# Sheet2.net
KiCad netlist of a schematic drawn in Altium Designer
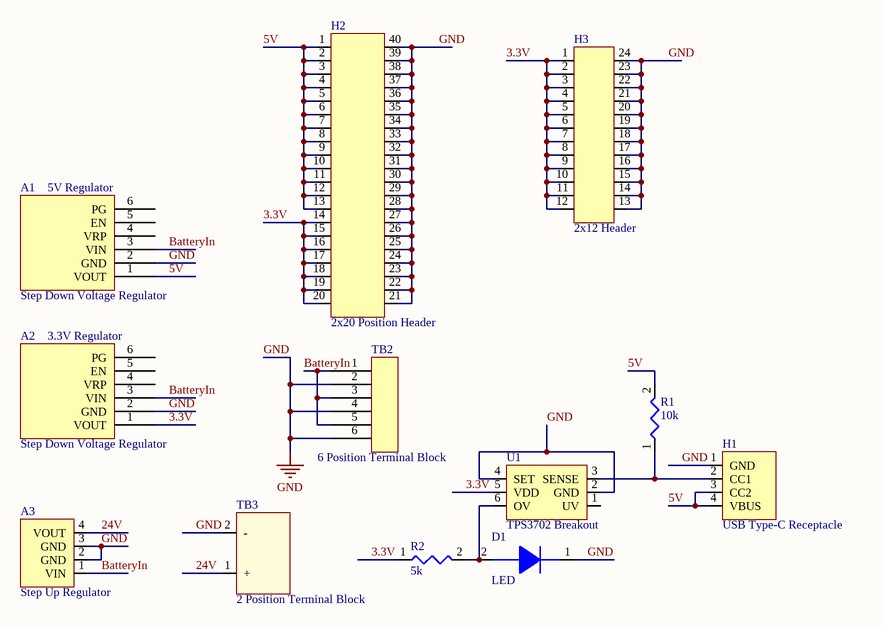
[diagram p0: Sheet2.SchDoc]

(export (version "E")
  (design (tool "Eeschema 10.0.6"))
  (components
    (comp (ref "A1")
      (value "Step Down Voltage Regulator")
      (footprint "New Volt Reg TEMPLATE")
      (libsource (lib "Schlib2") (part "Step Down Voltage Regulator"))
    )
    (comp (ref "A2")
      (value "Step Down Voltage Regulator")
      (footprint "New Volt Reg TEMPLATE")
      (libsource (lib "Schlib2") (part "Step Down Voltage Regulator"))
    )
    (comp (ref "A3")
      (value "Step Up Regulator")
      (footprint "24V STEP UP REGULATOR")
      (libsource (lib "Schlib2") (part "Step Up Regulator"))
    )
    (comp (ref "D1") (value "LED") (footprint "LED") (libsource (lib "Schlib2") (part "LED")))
    (comp (ref "H1")
      (value "USB Type-C Receptacle")
      (footprint "USB Type-C Receptacle")
      (libsource (lib "Schlib2") (part "USB Type-C Receptacle"))
    )
    (comp (ref "H2")
      (value "2x20 Position Header")
      (footprint "2x20 Header")
      (libsource (lib "Schlib2") (part "2x20 Position Header"))
    )
    (comp (ref "H3")
      (value "2x12 Header")
      (footprint "2x12 HEADER")
      (libsource (lib "Schlib2") (part "2x12 Header"))
    )
    (comp (ref "R1") (value "10k") (footprint "Resistor") (libsource (lib "Schlib2") (part "Resistor")))
    (comp (ref "R2") (value "5k") (footprint "Resistor") (libsource (lib "Schlib2") (part "Resistor")))
    (comp (ref "TB2")
      (value "6 Position Terminal Block")
      (footprint "NEW 6 Terminal")
      (libsource (lib "Schlib2") (part "6 Position Terminal Block"))
    )
    (comp (ref "TB3")
      (value "2 Position Terminal Block")
      (footprint "Terminal Block")
      (libsource (lib "Schlib2") (part "2 Position Terminal Block"))
    )
    (comp (ref "U1")
      (value "TPS3702 Breakout")
      (footprint "TPS3702 Breakout")
      (libsource (lib "Schlib2") (part "TPS3702 Breakout"))
    )
  )
  (nets
    (net (code "1") (name "/3.3V") (class "Default")
      (node (ref "A2") (pin "1") (pinfunction "VOUT_1") (pintype "passive"))
      (node (ref "H2") (pin "14") (pinfunction "14_14") (pintype "passive"))
      (node (ref "H2") (pin "15") (pinfunction "15_15") (pintype "passive"))
      (node (ref "H2") (pin "16") (pinfunction "16_16") (pintype "passive"))
      (node (ref "H2") (pin "17") (pinfunction "17_17") (pintype "passive"))
      (node (ref "H2") (pin "18") (pinfunction "18_18") (pintype "passive"))
      (node (ref "H2") (pin "19") (pinfunction "19_19") (pintype "passive"))
      (node (ref "H2") (pin "20") (pinfunction "20_20") (pintype "passive"))
      (node (ref "H3") (pin "1") (pinfunction "1_1") (pintype "passive"))
      (node (ref "H3") (pin "10") (pinfunction "10_10") (pintype "passive"))
      (node (ref "H3") (pin "11") (pinfunction "11_11") (pintype "passive"))
      (node (ref "H3") (pin "12") (pinfunction "12_12") (pintype "passive"))
      (node (ref "H3") (pin "2") (pinfunction "2_2") (pintype "passive"))
      (node (ref "H3") (pin "3") (pinfunction "3_3") (pintype "passive"))
      (node (ref "H3") (pin "4") (pinfunction "4_4") (pintype "passive"))
      (node (ref "H3") (pin "5") (pinfunction "5_5") (pintype "passive"))
      (node (ref "H3") (pin "6") (pinfunction "6_6") (pintype "passive"))
      (node (ref "H3") (pin "7") (pinfunction "7_7") (pintype "passive"))
      (node (ref "H3") (pin "8") (pinfunction "8_8") (pintype "passive"))
      (node (ref "H3") (pin "9") (pinfunction "9_9") (pintype "passive"))
      (node (ref "R2") (pin "1") (pinfunction "1_1") (pintype "passive"))
      (node (ref "U1") (pin "5") (pinfunction "VDD_5") (pintype "passive"))
    )
    (net (code "2") (name "/5V") (class "Default")
      (node (ref "A1") (pin "1") (pinfunction "VOUT_1") (pintype "passive"))
      (node (ref "H1") (pin "3") (pinfunction "CC2_3") (pintype "passive"))
      (node (ref "H1") (pin "4") (pinfunction "VBUS_4") (pintype "passive"))
      (node (ref "H2") (pin "1") (pinfunction "1_1") (pintype "passive"))
      (node (ref "H2") (pin "10") (pinfunction "10_10") (pintype "passive"))
      (node (ref "H2") (pin "11") (pinfunction "11_11") (pintype "passive"))
      (node (ref "H2") (pin "12") (pinfunction "12_12") (pintype "passive"))
      (node (ref "H2") (pin "13") (pinfunction "13_13") (pintype "passive"))
      (node (ref "H2") (pin "2") (pinfunction "2_2") (pintype "passive"))
      (node (ref "H2") (pin "3") (pinfunction "3_3") (pintype "passive"))
      (node (ref "H2") (pin "4") (pinfunction "4_4") (pintype "passive"))
      (node (ref "H2") (pin "5") (pinfunction "5_5") (pintype "passive"))
      (node (ref "H2") (pin "6") (pinfunction "6_6") (pintype "passive"))
      (node (ref "H2") (pin "7") (pinfunction "7_7") (pintype "passive"))
      (node (ref "H2") (pin "8") (pinfunction "8_8") (pintype "passive"))
      (node (ref "H2") (pin "9") (pinfunction "9_9") (pintype "passive"))
      (node (ref "R1") (pin "2") (pinfunction "2_2") (pintype "passive"))
    )
    (net (code "3") (name "/24V") (class "Default")
      (node (ref "A3") (pin "4") (pinfunction "VOUT_4") (pintype "passive"))
      (node (ref "TB3") (pin "1") (pinfunction "+_1") (pintype "passive"))
    )
    (net (code "4") (name "/BatteryIn") (class "Default")
      (node (ref "A1") (pin "3") (pinfunction "VIN_3") (pintype "passive"))
      (node (ref "A2") (pin "3") (pinfunction "VIN_3") (pintype "passive"))
      (node (ref "A3") (pin "1") (pinfunction "VIN_1") (pintype "passive"))
      (node (ref "TB2") (pin "1") (pintype "passive"))
      (node (ref "TB2") (pin "3") (pintype "passive"))
      (node (ref "TB2") (pin "5") (pintype "passive"))
    )
    (net (code "5") (name "GND") (class "Default")
      (node (ref "A1") (pin "2") (pinfunction "GND_2") (pintype "passive"))
      (node (ref "A2") (pin "2") (pinfunction "GND_2") (pintype "passive"))
      (node (ref "A3") (pin "2") (pinfunction "GND_2") (pintype "passive"))
      (node (ref "A3") (pin "3") (pinfunction "GND_3") (pintype "passive"))
      (node (ref "D1") (pin "1") (pinfunction "Anode_1") (pintype "passive"))
      (node (ref "H1") (pin "1") (pinfunction "GND_1") (pintype "passive"))
      (node (ref "H2") (pin "21") (pinfunction "21_21") (pintype "passive"))
      (node (ref "H2") (pin "22") (pinfunction "22_22") (pintype "passive"))
      (node (ref "H2") (pin "23") (pinfunction "23_23") (pintype "passive"))
      (node (ref "H2") (pin "24") (pinfunction "24_24") (pintype "passive"))
      (node (ref "H2") (pin "25") (pinfunction "25_25") (pintype "passive"))
      (node (ref "H2") (pin "26") (pinfunction "26_26") (pintype "passive"))
      (node (ref "H2") (pin "27") (pinfunction "27_27") (pintype "passive"))
      (node (ref "H2") (pin "28") (pinfunction "28_28") (pintype "passive"))
      (node (ref "H2") (pin "29") (pinfunction "29_29") (pintype "passive"))
      (node (ref "H2") (pin "30") (pinfunction "30_30") (pintype "passive"))
      (node (ref "H2") (pin "31") (pinfunction "31_31") (pintype "passive"))
      (node (ref "H2") (pin "32") (pinfunction "32_32") (pintype "passive"))
      (node (ref "H2") (pin "33") (pinfunction "33_33") (pintype "passive"))
      (node (ref "H2") (pin "34") (pinfunction "34_34") (pintype "passive"))
      (node (ref "H2") (pin "35") (pinfunction "35_35") (pintype "passive"))
      (node (ref "H2") (pin "36") (pinfunction "36_36") (pintype "passive"))
      (node (ref "H2") (pin "37") (pinfunction "37_37") (pintype "passive"))
      (node (ref "H2") (pin "38") (pinfunction "38_38") (pintype "passive"))
      (node (ref "H2") (pin "39") (pinfunction "39_39") (pintype "passive"))
      (node (ref "H2") (pin "40") (pinfunction "40_40") (pintype "passive"))
      (node (ref "H3") (pin "13") (pinfunction "13_13") (pintype "passive"))
      (node (ref "H3") (pin "14") (pinfunction "14_14") (pintype "passive"))
      (node (ref "H3") (pin "15") (pinfunction "15_15") (pintype "passive"))
      (node (ref "H3") (pin "16") (pinfunction "16_16") (pintype "passive"))
      (node (ref "H3") (pin "17") (pinfunction "17_17") (pintype "passive"))
      (node (ref "H3") (pin "18") (pinfunction "18_18") (pintype "passive"))
      (node (ref "H3") (pin "19") (pinfunction "19_19") (pintype "passive"))
      (node (ref "H3") (pin "20") (pinfunction "20_20") (pintype "passive"))
      (node (ref "H3") (pin "21") (pinfunction "21_21") (pintype "passive"))
      (node (ref "H3") (pin "22") (pinfunction "22_22") (pintype "passive"))
      (node (ref "H3") (pin "23") (pinfunction "23_23") (pintype "passive"))
      (node (ref "H3") (pin "24") (pinfunction "24_24") (pintype "passive"))
      (node (ref "TB2") (pin "2") (pintype "passive"))
      (node (ref "TB2") (pin "4") (pintype "passive"))
      (node (ref "TB2") (pin "6") (pintype "passive"))
      (node (ref "TB3") (pin "2") (pinfunction "-_2") (pintype "passive"))
      (node (ref "U1") (pin "2") (pinfunction "GND_2") (pintype "passive"))
      (node (ref "U1") (pin "4") (pinfunction "SET_4") (pintype "passive"))
    )
    (net (code "6") (name "Net-(D1-Cath)") (class "Default")
      (node (ref "D1") (pin "2") (pinfunction "Cath_2") (pintype "passive"))
      (node (ref "R2") (pin "2") (pinfunction "2_2") (pintype "passive"))
      (node (ref "U1") (pin "6") (pinfunction "OV_6") (pintype "passive"))
    )
    (net (code "7") (name "Net-(H1-CC1)") (class "Default")
      (node (ref "H1") (pin "2") (pinfunction "CC1_2") (pintype "passive"))
      (node (ref "R1") (pin "1") (pinfunction "1_1") (pintype "passive"))
      (node (ref "U1") (pin "3") (pinfunction "SENSE_3") (pintype "passive"))
    )
    (net (code "8") (name "unconnected-(A1-EN-Pad5)") (class "Default")
      (node (ref "A1") (pin "5") (pinfunction "EN_5") (pintype "passive"))
    )
    (net (code "9") (name "unconnected-(A1-PG-Pad6)") (class "Default")
      (node (ref "A1") (pin "6") (pinfunction "PG_6") (pintype "passive"))
    )
    (net (code "10") (name "unconnected-(A1-VRP-Pad4)") (class "Default")
      (node (ref "A1") (pin "4") (pinfunction "VRP_4") (pintype "passive"))
    )
    (net (code "11") (name "unconnected-(A2-EN-Pad5)") (class "Default")
      (node (ref "A2") (pin "5") (pinfunction "EN_5") (pintype "passive"))
    )
    (net (code "12") (name "unconnected-(A2-PG-Pad6)") (class "Default")
      (node (ref "A2") (pin "6") (pinfunction "PG_6") (pintype "passive"))
    )
    (net (code "13") (name "unconnected-(A2-VRP-Pad4)") (class "Default")
      (node (ref "A2") (pin "4") (pinfunction "VRP_4") (pintype "passive"))
    )
    (net (code "14") (name "unconnected-(U1-UV-Pad1)") (class "Default")
      (node (ref "U1") (pin "1") (pinfunction "UV_1") (pintype "passive"))
    )
  )
)
